# puissance.net
KiCad netlist of a schematic drawn in Altium Designer
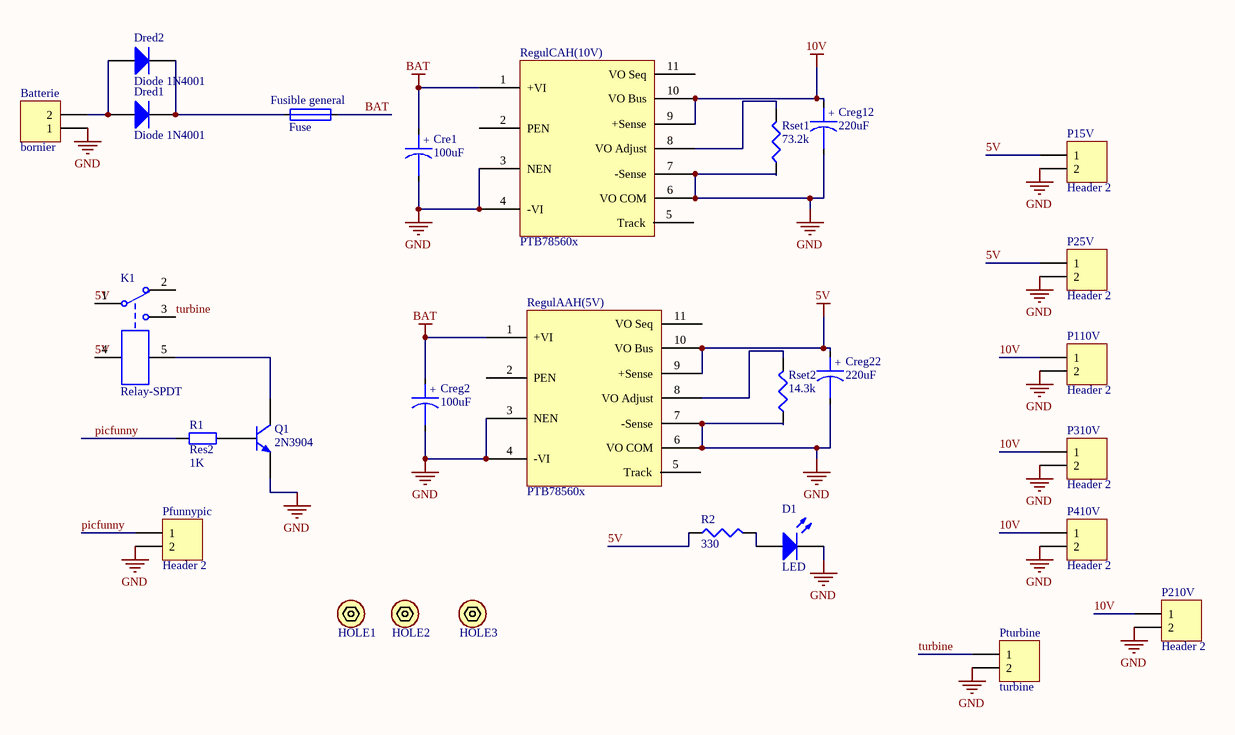
[diagram p0: puissance.SchDoc]

(export (version "E")
  (design (tool "Eeschema 10.0.6"))
  (components
    (comp (ref "Batterie")
      (value "bornier")
      (footprint "Bornier male coude 2 voies")
      (description "Header, 2-Pin")
      (fields (field (name "PUBLISHER") "Altium Limited"))
      (libsource (lib "") (part "Header 2_1"))
    )
    (comp (ref "Cre1")
      (value "100uF")
      (footprint "RB.1/.3")
      (description "Polarized Capacitor")
      (fields (field (name "Comment") "CAP Pol"))
      (libsource (lib "7Robot") (part "CAP Pol"))
    )
    (comp (ref "Creg2")
      (value "100uF")
      (footprint "RB.1/.3")
      (description "Polarized Capacitor")
      (fields (field (name "Comment") "CAP Pol"))
      (libsource (lib "7Robot") (part "CAP Pol"))
    )
    (comp (ref "Creg12")
      (value "220uF")
      (footprint "RB.1/.3")
      (description "Polarized Capacitor")
      (fields (field (name "Comment") "CAP Pol"))
      (libsource (lib "7Robot") (part "CAP Pol"))
    )
    (comp (ref "Creg22")
      (value "220uF")
      (footprint "RB.1/.3")
      (description "Polarized Capacitor")
      (fields (field (name "Comment") "CAP Pol"))
      (libsource (lib "7Robot") (part "CAP Pol"))
    )
    (comp (ref "D1")
      (value "LED")
      (footprint "LED 5mm red (dip)")
      (description "Typical LED")
      (fields (field (name "PUBLISHER") "Altium Limited"))
      (libsource (lib "7Robot") (part "LED"))
    )
    (comp (ref "Dred1")
      (value "Diode 1N4001")
      (footprint "DO-41")
      (description "1 Amp General Purpose Rectifier")
      (fields (field (name "PUBLISHER") "Altium Limited"))
      (libsource (lib "Miscellaneous Devices") (part "Diode 1N4001"))
    )
    (comp (ref "Dred2")
      (value "Diode 1N4001")
      (footprint "DO-41")
      (description "1 Amp General Purpose Rectifier")
      (fields (field (name "PUBLISHER") "Altium Limited"))
      (libsource (lib "Miscellaneous Devices") (part "Diode 1N4001"))
    )
    (comp (ref "Fusible general")
      (value "Fuse")
      (footprint "Fuse Holder 5x20mm")
      (libsource (lib "7Robot") (part "FUSE"))
    )
    (comp (ref "HOLE1")
      (value "Hole")
      (footprint "SCREW")
      (description "Mounting Hole for screws")
      (libsource (lib "7Robot") (part "Hole"))
    )
    (comp (ref "HOLE2")
      (value "Hole")
      (footprint "SCREW")
      (description "Mounting Hole for screws")
      (libsource (lib "7Robot") (part "Hole"))
    )
    (comp (ref "HOLE3")
      (value "Hole")
      (footprint "SCREW")
      (description "Mounting Hole for screws")
      (libsource (lib "7Robot") (part "Hole"))
    )
    (comp (ref "K1")
      (value "Relay-SPDT")
      (footprint "RELAY-SPST")
      (description "Single-Pole Dual-Throw Relay")
      (fields (field (name "PUBLISHER") "Altium Limited"))
      (libsource (lib "Miscellaneous Devices") (part "Relay-SPDT"))
    )
    (comp (ref "P15V")
      (value "Header 2")
      (footprint "Bornier male coude 2 voies")
      (description "Header, 2-Pin")
      (fields (field (name "PUBLISHER") "Altium Limited"))
      (libsource (lib "7Robot") (part "Header 2"))
    )
    (comp (ref "P25V")
      (value "Header 2")
      (footprint "Bornier male coude 2 voies")
      (description "Header, 2-Pin")
      (fields (field (name "PUBLISHER") "Altium Limited"))
      (libsource (lib "7Robot") (part "Header 2"))
    )
    (comp (ref "P110V")
      (value "Header 2")
      (footprint "Bornier male coude 2 voies")
      (description "Header, 2-Pin")
      (fields (field (name "PUBLISHER") "Altium Limited"))
      (libsource (lib "7Robot") (part "Header 2"))
    )
    (comp (ref "P210V")
      (value "Header 2")
      (footprint "Bornier male coude 2 voies")
      (description "Header, 2-Pin")
      (fields (field (name "PUBLISHER") "Altium Limited"))
      (libsource (lib "7Robot") (part "Header 2"))
    )
    (comp (ref "P310V")
      (value "Header 2")
      (footprint "Bornier male coude 2 voies")
      (description "Header, 2-Pin")
      (fields (field (name "PUBLISHER") "Altium Limited"))
      (libsource (lib "7Robot") (part "Header 2"))
    )
    (comp (ref "P410V")
      (value "Header 2")
      (footprint "Bornier male coude 2 voies")
      (description "Header, 2-Pin")
      (fields (field (name "PUBLISHER") "Altium Limited"))
      (libsource (lib "7Robot") (part "Header 2"))
    )
    (comp (ref "Pfunnypic")
      (value "Header 2")
      (footprint "Bornier male coude 2 voies")
      (description "Header, 2-Pin")
      (fields (field (name "PUBLISHER") "Altium Limited"))
      (libsource (lib "7Robot") (part "Header 2"))
    )
    (comp (ref "Pturbine")
      (value "turbine")
      (footprint "Bornier male coude 2 voies")
      (description "Header, 2-Pin")
      (fields (field (name "PUBLISHER") "Altium Limited"))
      (libsource (lib "7Robot") (part "Header 2"))
    )
    (comp (ref "Q1")
      (value "2N3904")
      (footprint "TO-92A")
      (description "NPN General Purpose Amplifier")
      (fields (field (name "PUBLISHER") "Altium Limited"))
      (libsource (lib "Miscellaneous Devices") (part "2N3904"))
    )
    (comp (ref "R1")
      (value "Res2")
      (footprint "AXIAL-0.4")
      (description "Resistor")
      (fields (field (name "ALTIUM_VALUE") "1K") (field (name "PUBLISHER") "Altium Limited"))
      (libsource (lib "Miscellaneous Devices") (part "Res2"))
    )
    (comp (ref "R2")
      (value "330")
      (footprint "AXIAL0.8")
      (description "Resistor")
      (fields (field (name "Comment") "RES") (field (name "PUBLISHER") "Altium Limited"))
      (libsource (lib "7Robot") (part "RES"))
    )
    (comp (ref "RegulAAH(5V)")
      (value "PTB78560x")
      (footprint "PTB78560x")
      (description "Texas Instruments Regulators")
      (libsource (lib "7Robot") (part "PTB78560x"))
    )
    (comp (ref "RegulCAH(10V)")
      (value "PTB78560x")
      (footprint "PTB78560x")
      (description "Texas Instruments Regulators")
      (libsource (lib "7Robot") (part "PTB78560x"))
    )
    (comp (ref "Rset1")
      (value "73.2k")
      (footprint "AXIAL0.8")
      (description "Resistor")
      (fields (field (name "Comment") "RES") (field (name "PUBLISHER") "Altium Limited"))
      (libsource (lib "7Robot") (part "RES"))
    )
    (comp (ref "Rset2")
      (value "14.3k")
      (footprint "AXIAL0.8")
      (description "Resistor")
      (fields (field (name "Comment") "RES") (field (name "PUBLISHER") "Altium Limited"))
      (libsource (lib "7Robot") (part "RES"))
    )
  )
  (nets
    (net (code "1") (name "/picfunny") (class "Default")
      (node (ref "Pfunnypic") (pin "1") (pinfunction "1_1") (pintype "passive"))
      (node (ref "R1") (pin "1") (pinfunction "1_1") (pintype "passive"))
    )
    (net (code "2") (name "/turbine") (class "Default")
      (node (ref "K1") (pin "3") (pinfunction "3_3") (pintype "passive"))
      (node (ref "Pturbine") (pin "1") (pinfunction "1_1") (pintype "passive"))
    )
    (net (code "3") (name "5V") (class "Default")
      (node (ref "Creg22") (pin "1") (pinfunction "1_1") (pintype "passive"))
      (node (ref "K1") (pin "1") (pinfunction "1_1") (pintype "passive"))
      (node (ref "K1") (pin "4") (pinfunction "4_4") (pintype "passive"))
      (node (ref "P15V") (pin "1") (pinfunction "1_1") (pintype "passive"))
      (node (ref "P25V") (pin "1") (pinfunction "1_1") (pintype "passive"))
      (node (ref "R2") (pin "1") (pinfunction "1_1") (pintype "passive"))
      (node (ref "RegulAAH(5V)") (pin "10") (pinfunction "VO_Bus_10") (pintype "passive"))
      (node (ref "RegulAAH(5V)") (pin "9") (pinfunction "+Sense_9") (pintype "passive"))
    )
    (net (code "4") (name "10V") (class "Default")
      (node (ref "Creg12") (pin "1") (pinfunction "1_1") (pintype "passive"))
      (node (ref "P110V") (pin "1") (pinfunction "1_1") (pintype "passive"))
      (node (ref "P210V") (pin "1") (pinfunction "1_1") (pintype "passive"))
      (node (ref "P310V") (pin "1") (pinfunction "1_1") (pintype "passive"))
      (node (ref "P410V") (pin "1") (pinfunction "1_1") (pintype "passive"))
      (node (ref "RegulCAH(10V)") (pin "10") (pinfunction "VO_Bus_10") (pintype "passive"))
      (node (ref "RegulCAH(10V)") (pin "9") (pinfunction "+Sense_9") (pintype "passive"))
    )
    (net (code "5") (name "BAT") (class "Default")
      (node (ref "Cre1") (pin "1") (pinfunction "1_1") (pintype "passive"))
      (node (ref "Creg2") (pin "1") (pinfunction "1_1") (pintype "passive"))
      (node (ref "Fusible general") (pin "2") (pinfunction "2_2") (pintype "passive"))
      (node (ref "RegulAAH(5V)") (pin "1") (pinfunction "+VI_1") (pintype "power_in"))
      (node (ref "RegulCAH(10V)") (pin "1") (pinfunction "+VI_1") (pintype "power_in"))
    )
    (net (code "6") (name "GND") (class "Default")
      (node (ref "Batterie") (pin "1") (pinfunction "1_1") (pintype "passive"))
      (node (ref "Cre1") (pin "2") (pinfunction "2_2") (pintype "passive"))
      (node (ref "Creg12") (pin "2") (pinfunction "2_2") (pintype "passive"))
      (node (ref "Creg2") (pin "2") (pinfunction "2_2") (pintype "passive"))
      (node (ref "Creg22") (pin "2") (pinfunction "2_2") (pintype "passive"))
      (node (ref "D1") (pin "K") (pinfunction "K_K") (pintype "passive"))
      (node (ref "P110V") (pin "2") (pinfunction "2_2") (pintype "passive"))
      (node (ref "P15V") (pin "2") (pinfunction "2_2") (pintype "passive"))
      (node (ref "P210V") (pin "2") (pinfunction "2_2") (pintype "passive"))
      (node (ref "P25V") (pin "2") (pinfunction "2_2") (pintype "passive"))
      (node (ref "P310V") (pin "2") (pinfunction "2_2") (pintype "passive"))
      (node (ref "P410V") (pin "2") (pinfunction "2_2") (pintype "passive"))
      (node (ref "Pfunnypic") (pin "2") (pinfunction "2_2") (pintype "passive"))
      (node (ref "Pturbine") (pin "2") (pinfunction "2_2") (pintype "passive"))
      (node (ref "Q1") (pin "1") (pinfunction "E_1") (pintype "passive"))
      (node (ref "RegulAAH(5V)") (pin "3") (pinfunction "NEN_3") (pintype "power_in"))
      (node (ref "RegulAAH(5V)") (pin "4") (pinfunction "-VI_4") (pintype "power_in"))
      (node (ref "RegulAAH(5V)") (pin "6") (pinfunction "VO_COM_6") (pintype "passive"))
      (node (ref "RegulAAH(5V)") (pin "7") (pinfunction "-Sense_7") (pintype "passive"))
      (node (ref "RegulCAH(10V)") (pin "3") (pinfunction "NEN_3") (pintype "power_in"))
      (node (ref "RegulCAH(10V)") (pin "4") (pinfunction "-VI_4") (pintype "power_in"))
      (node (ref "RegulCAH(10V)") (pin "6") (pinfunction "VO_COM_6") (pintype "passive"))
      (node (ref "RegulCAH(10V)") (pin "7") (pinfunction "-Sense_7") (pintype "passive"))
      (node (ref "Rset1") (pin "1") (pinfunction "1_1") (pintype "passive"))
      (node (ref "Rset2") (pin "1") (pinfunction "1_1") (pintype "passive"))
    )
    (net (code "7") (name "Net-(D1-PadA)") (class "Default")
      (node (ref "D1") (pin "A") (pinfunction "A_A") (pintype "passive"))
      (node (ref "R2") (pin "2") (pinfunction "2_2") (pintype "passive"))
    )
    (net (code "8") (name "Net-(Dred1-A)") (class "Default")
      (node (ref "Batterie") (pin "2") (pinfunction "2_2") (pintype "passive"))
      (node (ref "Dred1") (pin "1") (pinfunction "A_1") (pintype "passive"))
      (node (ref "Dred2") (pin "1") (pinfunction "A_1") (pintype "passive"))
    )
    (net (code "9") (name "Net-(Dred1-K)") (class "Default")
      (node (ref "Dred1") (pin "2") (pinfunction "K_2") (pintype "passive"))
      (node (ref "Dred2") (pin "2") (pinfunction "K_2") (pintype "passive"))
      (node (ref "Fusible general") (pin "1") (pinfunction "1_1") (pintype "passive"))
    )
    (net (code "10") (name "Net-(Q1-B)") (class "Default")
      (node (ref "Q1") (pin "2") (pinfunction "B_2") (pintype "passive"))
      (node (ref "R1") (pin "2") (pinfunction "2_2") (pintype "passive"))
    )
    (net (code "11") (name "Net-(Q1-C)") (class "Default")
      (node (ref "K1") (pin "5") (pinfunction "5_5") (pintype "passive"))
      (node (ref "Q1") (pin "3") (pinfunction "C_3") (pintype "passive"))
    )
    (net (code "12") (name "Net-(RegulAAH(5V)-VO_Adjust)") (class "Default")
      (node (ref "RegulAAH(5V)") (pin "8") (pinfunction "VO_Adjust_8") (pintype "passive"))
      (node (ref "Rset2") (pin "2") (pinfunction "2_2") (pintype "passive"))
    )
    (net (code "13") (name "Net-(RegulCAH(10V)-VO_Adjust)") (class "Default")
      (node (ref "RegulCAH(10V)") (pin "8") (pinfunction "VO_Adjust_8") (pintype "passive"))
      (node (ref "Rset1") (pin "2") (pinfunction "2_2") (pintype "passive"))
    )
    (net (code "14") (name "unconnected-(HOLE1-Hole-Pad1)") (class "Default")
      (node (ref "HOLE1") (pin "1") (pinfunction "Hole_1") (pintype "passive"))
    )
    (net (code "15") (name "unconnected-(HOLE2-Hole-Pad1)") (class "Default")
      (node (ref "HOLE2") (pin "1") (pinfunction "Hole_1") (pintype "passive"))
    )
    (net (code "16") (name "unconnected-(HOLE3-Hole-Pad1)") (class "Default")
      (node (ref "HOLE3") (pin "1") (pinfunction "Hole_1") (pintype "passive"))
    )
    (net (code "17") (name "unconnected-(K1-Pad2)") (class "Default")
      (node (ref "K1") (pin "2") (pinfunction "2_2") (pintype "passive"))
    )
    (net (code "18") (name "unconnected-(RegulAAH(5V)-PEN-Pad2)") (class "Default")
      (node (ref "RegulAAH(5V)") (pin "2") (pinfunction "PEN_2") (pintype "power_in"))
    )
    (net (code "19") (name "unconnected-(RegulAAH(5V)-Track-Pad5)") (class "Default")
      (node (ref "RegulAAH(5V)") (pin "5") (pinfunction "Track_5") (pintype "power_in"))
    )
    (net (code "20") (name "unconnected-(RegulAAH(5V)-VO_Seq-Pad11)") (class "Default")
      (node (ref "RegulAAH(5V)") (pin "11") (pinfunction "VO_Seq_11") (pintype "passive"))
    )
    (net (code "21") (name "unconnected-(RegulCAH(10V)-PEN-Pad2)") (class "Default")
      (node (ref "RegulCAH(10V)") (pin "2") (pinfunction "PEN_2") (pintype "power_in"))
    )
    (net (code "22") (name "unconnected-(RegulCAH(10V)-Track-Pad5)") (class "Default")
      (node (ref "RegulCAH(10V)") (pin "5") (pinfunction "Track_5") (pintype "power_in"))
    )
    (net (code "23") (name "unconnected-(RegulCAH(10V)-VO_Seq-Pad11)") (class "Default")
      (node (ref "RegulCAH(10V)") (pin "11") (pinfunction "VO_Seq_11") (pintype "passive"))
    )
  )
)
